# iSystem-jumpers.net
KiCad netlist of a schematic drawn in Altium Designer
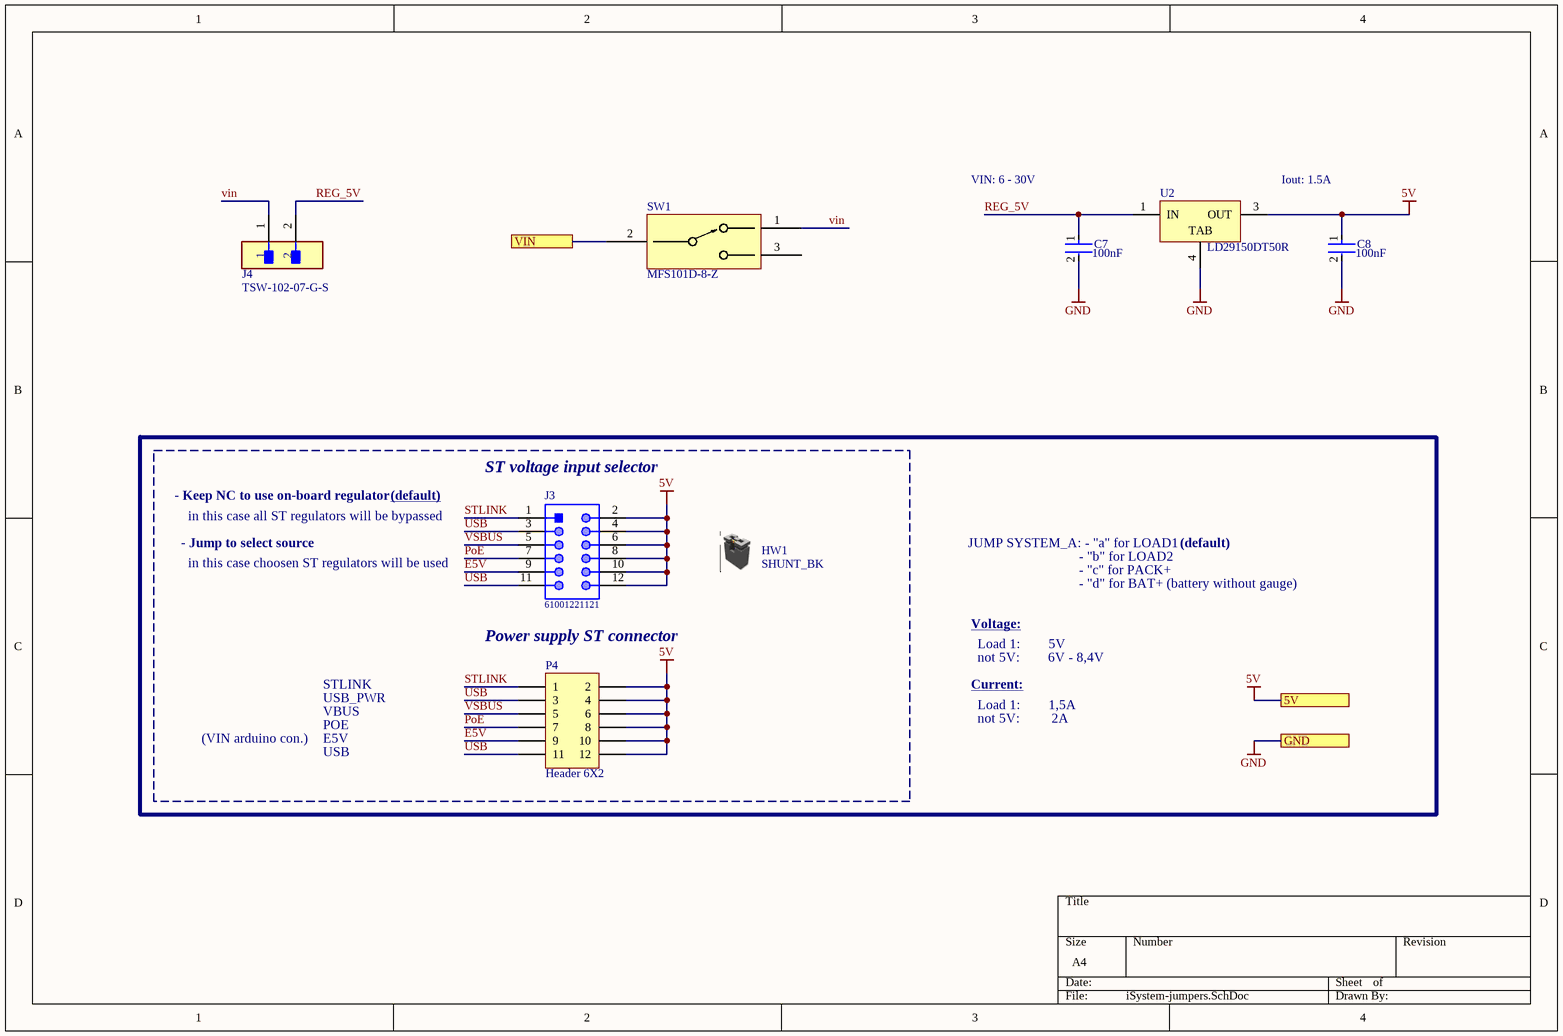
[diagram p0: iSystem-jumpers.SchDoc]

(export (version "E")
  (design (tool "Eeschema 10.0.6"))
  (components
    (comp (ref "C7")
      (value "100nF")
      (footprint "FP-CGA3E-0_3-0_1-IPC_A")
      (description "Cap Ceramic 100nF 50V X7R 10% Pad SMD 0603 +125°C Automotive T/R")
      (fields (field (name "TOLERANCE") "10%") (field (name "VOLTAGE") "50V"))
      (libsource (lib "Altium Content Vault") (part "b4654b650e69147ec39a6b967a45e02"))
    )
    (comp (ref "C8")
      (value "100nF")
      (footprint "FP-CGA3E-0_3-0_1-IPC_A")
      (description "Cap Ceramic 100nF 50V X7R 10% Pad SMD 0603 +125°C Automotive T/R")
      (fields (field (name "TOLERANCE") "10%") (field (name "VOLTAGE") "50V"))
      (libsource (lib "Altium Content Vault") (part "b4654b650e69147ec39a6b967a45e02"))
    )
    (comp (ref "HW1")
      (value "SHUNT_BK")
      (footprint "NA")
      (description "SHUNT, 2.54mm, height 6.10mm, BLACK")
      (fields
        (field (name "INTERNAL_PART_NUMBER") "MCD-00122")
        (field (name "MANUFACTURER_PART_NUMBER") "SNT-100-BK-G")
        (field (name "PROVIDED_BY") "Subcon")
      )
      (libsource (lib "MCD_PARTS_database") (part "Shunt Black 2.54mm"))
    )
    (comp (ref "J3")
      (value "61001221121")
      (footprint "61001221121")
      (description "SMT Vertical Pin Header WR-PHD, Pitch 2.54 mm, Dual Row, 12 pins")
      (fields (field (name "MANUFACTURER") "Wurth Elektronik") (field (name "PUBLISHER") "WurthElektronik"))
      (libsource (lib "Altium Content Vault") (part "WE-CN-2P-M-R12"))
    )
    (comp (ref "J4")
      (value "TSW-102-07-G-S")
      (footprint "FP-TSW-102-07-G-S-MFG")
      (description "CONN HEADER VERT 2POS 2.54MM")
      (fields
        (field (name "MANUFACTURER") "Samtec")
        (field (name "OCTOPART") "https://octopart.com/tsw-102-07-g-s-samtec-272197")
      )
      (libsource (lib "Altium Content Vault") (part "3bc925449376181038e59eaffc5286c"))
    )
    (comp (ref "P4")
      (value "Header 6X2")
      (footprint "HDR2X6")
      (description "Header, 6-Pin, Dual row")
      (fields (field (name "PUBLISHER") "Altium Limited"))
      (libsource (lib "Miscellaneous Connectors") (part "Header 6X2"))
    )
    (comp (ref "SW1")
      (value "MFS101D-8-Z")
      (footprint "MFS101D-8-Z")
      (libsource (lib "Götterdämmerung") (part "MFS101D-8-Z"))
    )
    (comp (ref "U2")
      (value "LD29150DT50R")
      (footprint "TO-252_M")
      (description "1.5A, Very-Low Drop Voltage Regulator, 5V, 3-Pin DPAK")
      (libsource (lib "Altium Content Vault") (part "PM-REG-LD29150-SOT3"))
    )
  )
  (nets
    (net (code "1") (name "/E5V") (class "Default")
      (node (ref "J3") (pin "9") (pinfunction "9_9") (pintype "passive"))
      (node (ref "P4") (pin "9") (pinfunction "9_9") (pintype "passive"))
    )
    (net (code "2") (name "/PoE") (class "Default")
      (node (ref "J3") (pin "7") (pinfunction "7_7") (pintype "passive"))
      (node (ref "P4") (pin "7") (pinfunction "7_7") (pintype "passive"))
    )
    (net (code "3") (name "/REG_5V") (class "Default")
      (node (ref "C7") (pin "1") (pinfunction "1_1") (pintype "passive"))
      (node (ref "J4") (pin "2") (pinfunction "2_2") (pintype "passive"))
      (node (ref "U2") (pin "1") (pinfunction "IN_1") (pintype "power_in"))
    )
    (net (code "4") (name "/STLINK") (class "Default")
      (node (ref "J3") (pin "1") (pinfunction "1_1") (pintype "passive"))
      (node (ref "P4") (pin "1") (pinfunction "1_1") (pintype "passive"))
    )
    (net (code "5") (name "/USB") (class "Default")
      (node (ref "J3") (pin "11") (pinfunction "11_11") (pintype "passive"))
      (node (ref "J3") (pin "3") (pinfunction "3_3") (pintype "passive"))
      (node (ref "P4") (pin "11") (pinfunction "11_11") (pintype "passive"))
      (node (ref "P4") (pin "3") (pinfunction "3_3") (pintype "passive"))
    )
    (net (code "6") (name "/VIN") (class "Default") (node (ref "SW1") (pin "2") (pintype "passive")))
    (net (code "7") (name "/VSBUS") (class "Default")
      (node (ref "J3") (pin "5") (pinfunction "5_5") (pintype "passive"))
      (node (ref "P4") (pin "5") (pinfunction "5_5") (pintype "passive"))
    )
    (net (code "8") (name "/vin") (class "Default")
      (node (ref "J4") (pin "1") (pinfunction "1_1") (pintype "passive"))
      (node (ref "SW1") (pin "1") (pintype "passive"))
    )
    (net (code "9") (name "5V") (class "Default")
      (node (ref "C8") (pin "1") (pinfunction "1_1") (pintype "passive"))
      (node (ref "J3") (pin "10") (pinfunction "10_10") (pintype "passive"))
      (node (ref "J3") (pin "12") (pinfunction "12_12") (pintype "passive"))
      (node (ref "J3") (pin "2") (pinfunction "2_2") (pintype "passive"))
      (node (ref "J3") (pin "4") (pinfunction "4_4") (pintype "passive"))
      (node (ref "J3") (pin "6") (pinfunction "6_6") (pintype "passive"))
      (node (ref "J3") (pin "8") (pinfunction "8_8") (pintype "passive"))
      (node (ref "P4") (pin "10") (pinfunction "10_10") (pintype "passive"))
      (node (ref "P4") (pin "12") (pinfunction "12_12") (pintype "passive"))
      (node (ref "P4") (pin "2") (pinfunction "2_2") (pintype "passive"))
      (node (ref "P4") (pin "4") (pinfunction "4_4") (pintype "passive"))
      (node (ref "P4") (pin "6") (pinfunction "6_6") (pintype "passive"))
      (node (ref "P4") (pin "8") (pinfunction "8_8") (pintype "passive"))
      (node (ref "U2") (pin "3") (pinfunction "OUT_3") (pintype "power_in"))
    )
    (net (code "10") (name "GND") (class "Default")
      (node (ref "C7") (pin "2") (pinfunction "2_2") (pintype "passive"))
      (node (ref "C8") (pin "2") (pinfunction "2_2") (pintype "passive"))
      (node (ref "U2") (pin "4") (pinfunction "TAB_4") (pintype "passive"))
    )
    (net (code "11") (name "unconnected-(SW1-Pad3)") (class "Default")
      (node (ref "SW1") (pin "3") (pintype "passive"))
    )
  )
)
